# tester1.net
KiCad netlist of a schematic drawn in EAGLE
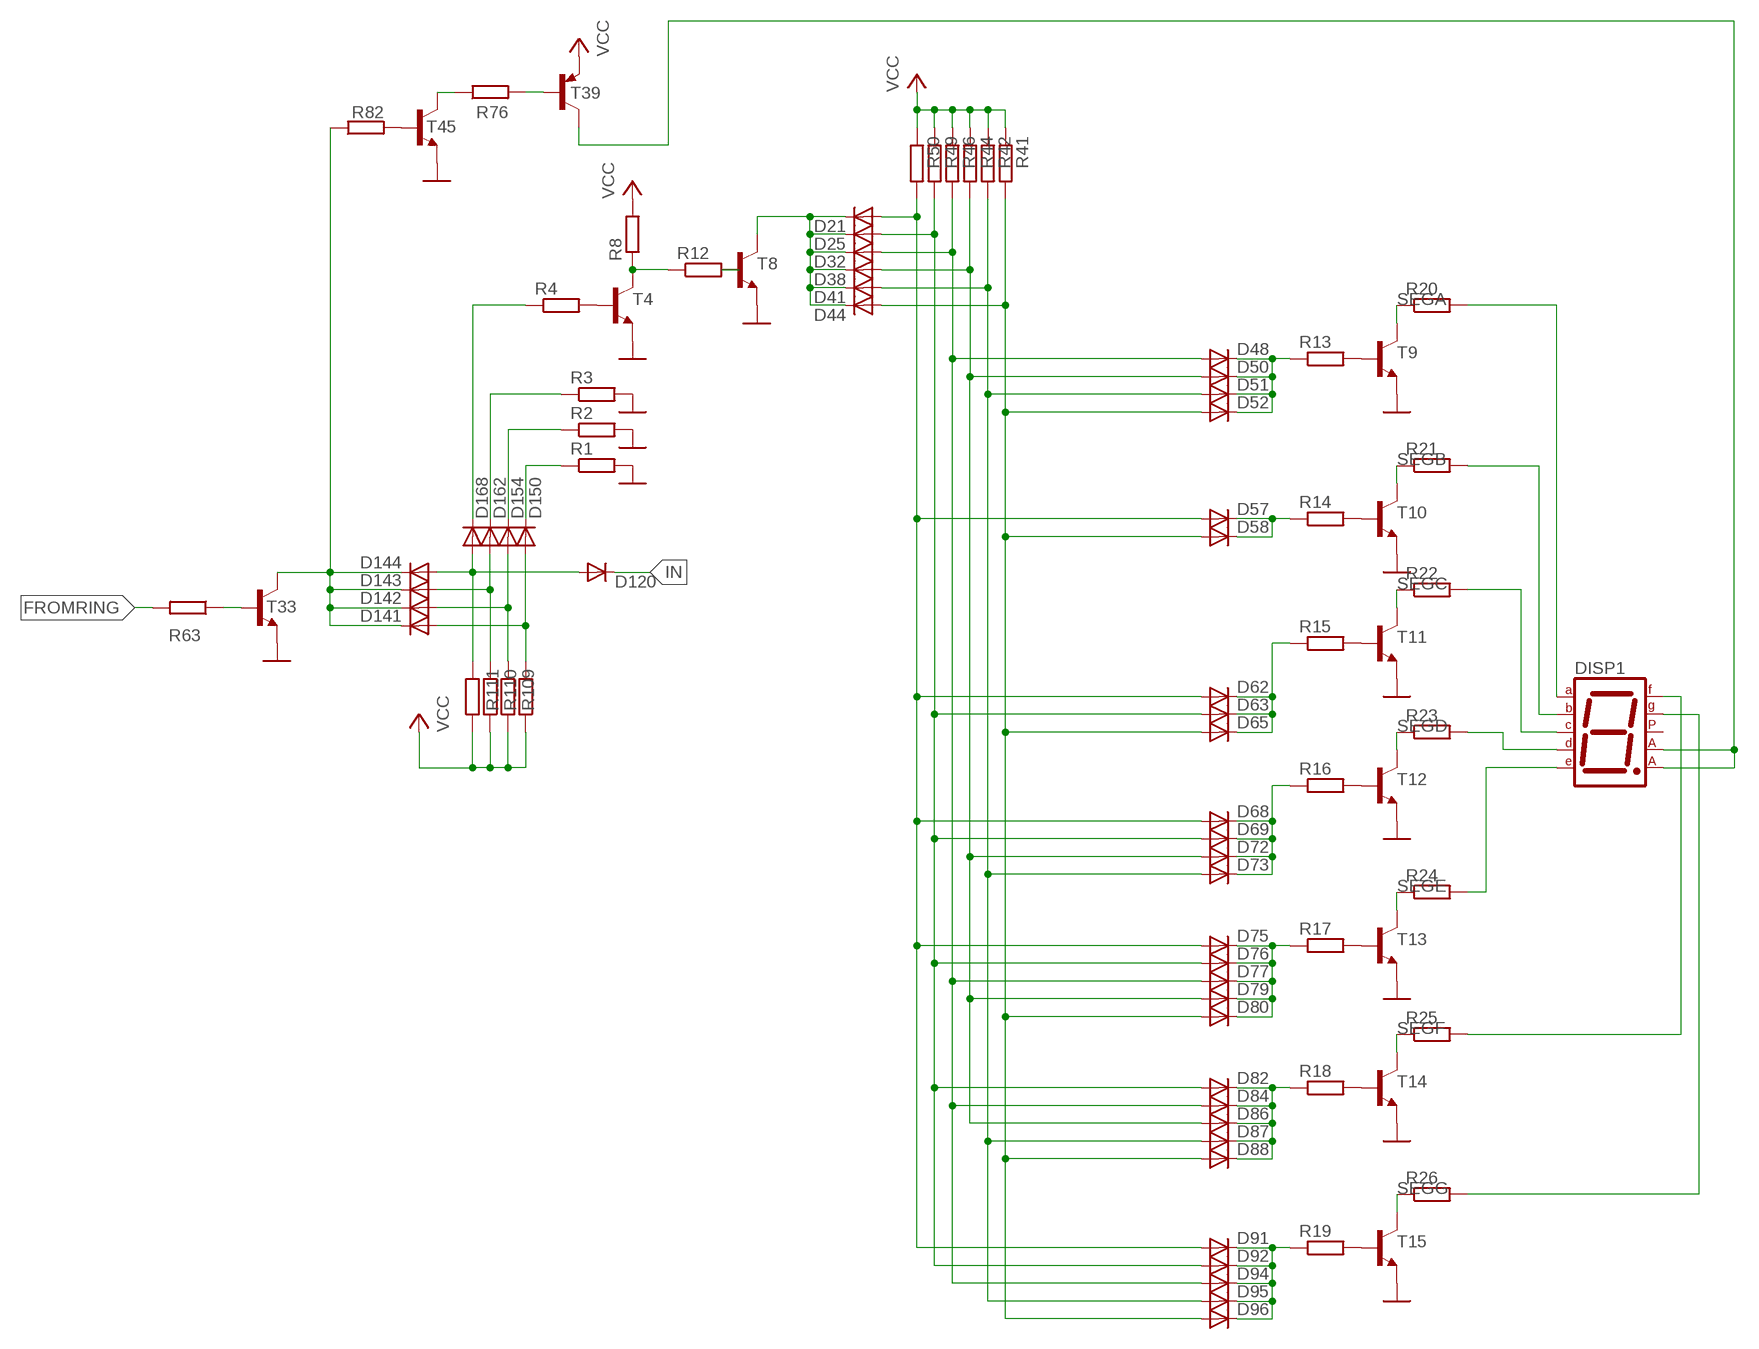
[diagram p0: schematic, sheet 1]

(export (version "E")
  (design (tool "Eeschema 10.0.6"))
  (components
    (comp (ref "D21")
      (value "SMALL_DIODEDO35-7")
      (footprint "eagle-import:DO35-7")
      (libsource (lib "eagle-import") (part "SMALL_DIODEDO35-7"))
    )
    (comp (ref "D25")
      (value "SMALL_DIODEDO35-7")
      (footprint "eagle-import:DO35-7")
      (libsource (lib "eagle-import") (part "SMALL_DIODEDO35-7"))
    )
    (comp (ref "D32")
      (value "SMALL_DIODEDO35-7")
      (footprint "eagle-import:DO35-7")
      (libsource (lib "eagle-import") (part "SMALL_DIODEDO35-7"))
    )
    (comp (ref "D38")
      (value "SMALL_DIODEDO35-7")
      (footprint "eagle-import:DO35-7")
      (libsource (lib "eagle-import") (part "SMALL_DIODEDO35-7"))
    )
    (comp (ref "D41")
      (value "SMALL_DIODEDO35-7")
      (footprint "eagle-import:DO35-7")
      (libsource (lib "eagle-import") (part "SMALL_DIODEDO35-7"))
    )
    (comp (ref "D44")
      (value "SMALL_DIODEDO35-7")
      (footprint "eagle-import:DO35-7")
      (libsource (lib "eagle-import") (part "SMALL_DIODEDO35-7"))
    )
    (comp (ref "D48")
      (value "SMALL_DIODEDO35-7")
      (footprint "eagle-import:DO35-7")
      (libsource (lib "eagle-import") (part "SMALL_DIODEDO35-7"))
    )
    (comp (ref "D50")
      (value "SMALL_DIODEDO35-7")
      (footprint "eagle-import:DO35-7")
      (libsource (lib "eagle-import") (part "SMALL_DIODEDO35-7"))
    )
    (comp (ref "D51")
      (value "SMALL_DIODEDO35-7")
      (footprint "eagle-import:DO35-7")
      (libsource (lib "eagle-import") (part "SMALL_DIODEDO35-7"))
    )
    (comp (ref "D52")
      (value "SMALL_DIODEDO35-7")
      (footprint "eagle-import:DO35-7")
      (libsource (lib "eagle-import") (part "SMALL_DIODEDO35-7"))
    )
    (comp (ref "D57")
      (value "SMALL_DIODEDO35-7")
      (footprint "eagle-import:DO35-7")
      (libsource (lib "eagle-import") (part "SMALL_DIODEDO35-7"))
    )
    (comp (ref "D58")
      (value "SMALL_DIODEDO35-7")
      (footprint "eagle-import:DO35-7")
      (libsource (lib "eagle-import") (part "SMALL_DIODEDO35-7"))
    )
    (comp (ref "D62")
      (value "SMALL_DIODEDO35-7")
      (footprint "eagle-import:DO35-7")
      (libsource (lib "eagle-import") (part "SMALL_DIODEDO35-7"))
    )
    (comp (ref "D63")
      (value "SMALL_DIODEDO35-7")
      (footprint "eagle-import:DO35-7")
      (libsource (lib "eagle-import") (part "SMALL_DIODEDO35-7"))
    )
    (comp (ref "D65")
      (value "SMALL_DIODEDO35-7")
      (footprint "eagle-import:DO35-7")
      (libsource (lib "eagle-import") (part "SMALL_DIODEDO35-7"))
    )
    (comp (ref "D68")
      (value "SMALL_DIODEDO35-7")
      (footprint "eagle-import:DO35-7")
      (libsource (lib "eagle-import") (part "SMALL_DIODEDO35-7"))
    )
    (comp (ref "D69")
      (value "SMALL_DIODEDO35-7")
      (footprint "eagle-import:DO35-7")
      (libsource (lib "eagle-import") (part "SMALL_DIODEDO35-7"))
    )
    (comp (ref "D72")
      (value "SMALL_DIODEDO35-7")
      (footprint "eagle-import:DO35-7")
      (libsource (lib "eagle-import") (part "SMALL_DIODEDO35-7"))
    )
    (comp (ref "D73")
      (value "SMALL_DIODEDO35-7")
      (footprint "eagle-import:DO35-7")
      (libsource (lib "eagle-import") (part "SMALL_DIODEDO35-7"))
    )
    (comp (ref "D75")
      (value "SMALL_DIODEDO35-7")
      (footprint "eagle-import:DO35-7")
      (libsource (lib "eagle-import") (part "SMALL_DIODEDO35-7"))
    )
    (comp (ref "D76")
      (value "SMALL_DIODEDO35-7")
      (footprint "eagle-import:DO35-7")
      (libsource (lib "eagle-import") (part "SMALL_DIODEDO35-7"))
    )
    (comp (ref "D77")
      (value "SMALL_DIODEDO35-7")
      (footprint "eagle-import:DO35-7")
      (libsource (lib "eagle-import") (part "SMALL_DIODEDO35-7"))
    )
    (comp (ref "D79")
      (value "SMALL_DIODEDO35-7")
      (footprint "eagle-import:DO35-7")
      (libsource (lib "eagle-import") (part "SMALL_DIODEDO35-7"))
    )
    (comp (ref "D80")
      (value "SMALL_DIODEDO35-7")
      (footprint "eagle-import:DO35-7")
      (libsource (lib "eagle-import") (part "SMALL_DIODEDO35-7"))
    )
    (comp (ref "D82")
      (value "SMALL_DIODEDO35-7")
      (footprint "eagle-import:DO35-7")
      (libsource (lib "eagle-import") (part "SMALL_DIODEDO35-7"))
    )
    (comp (ref "D84")
      (value "SMALL_DIODEDO35-7")
      (footprint "eagle-import:DO35-7")
      (libsource (lib "eagle-import") (part "SMALL_DIODEDO35-7"))
    )
    (comp (ref "D86")
      (value "SMALL_DIODEDO35-7")
      (footprint "eagle-import:DO35-7")
      (libsource (lib "eagle-import") (part "SMALL_DIODEDO35-7"))
    )
    (comp (ref "D87")
      (value "SMALL_DIODEDO35-7")
      (footprint "eagle-import:DO35-7")
      (libsource (lib "eagle-import") (part "SMALL_DIODEDO35-7"))
    )
    (comp (ref "D88")
      (value "SMALL_DIODEDO35-7")
      (footprint "eagle-import:DO35-7")
      (libsource (lib "eagle-import") (part "SMALL_DIODEDO35-7"))
    )
    (comp (ref "D91")
      (value "SMALL_DIODEDO35-7")
      (footprint "eagle-import:DO35-7")
      (libsource (lib "eagle-import") (part "SMALL_DIODEDO35-7"))
    )
    (comp (ref "D92")
      (value "SMALL_DIODEDO35-7")
      (footprint "eagle-import:DO35-7")
      (libsource (lib "eagle-import") (part "SMALL_DIODEDO35-7"))
    )
    (comp (ref "D94")
      (value "SMALL_DIODEDO35-7")
      (footprint "eagle-import:DO35-7")
      (libsource (lib "eagle-import") (part "SMALL_DIODEDO35-7"))
    )
    (comp (ref "D95")
      (value "SMALL_DIODEDO35-7")
      (footprint "eagle-import:DO35-7")
      (libsource (lib "eagle-import") (part "SMALL_DIODEDO35-7"))
    )
    (comp (ref "D96")
      (value "SMALL_DIODEDO35-7")
      (footprint "eagle-import:DO35-7")
      (libsource (lib "eagle-import") (part "SMALL_DIODEDO35-7"))
    )
    (comp (ref "D120")
      (value "SMALL_DIODEDO35-7")
      (footprint "eagle-import:DO35-7")
      (libsource (lib "eagle-import") (part "SMALL_DIODEDO35-7"))
    )
    (comp (ref "D141")
      (value "SMALL_DIODEDO35-7")
      (footprint "eagle-import:DO35-7")
      (libsource (lib "eagle-import") (part "SMALL_DIODEDO35-7"))
    )
    (comp (ref "D142")
      (value "SMALL_DIODEDO35-7")
      (footprint "eagle-import:DO35-7")
      (libsource (lib "eagle-import") (part "SMALL_DIODEDO35-7"))
    )
    (comp (ref "D143")
      (value "SMALL_DIODEDO35-7")
      (footprint "eagle-import:DO35-7")
      (libsource (lib "eagle-import") (part "SMALL_DIODEDO35-7"))
    )
    (comp (ref "D144")
      (value "SMALL_DIODEDO35-7")
      (footprint "eagle-import:DO35-7")
      (libsource (lib "eagle-import") (part "SMALL_DIODEDO35-7"))
    )
    (comp (ref "D150")
      (value "SMALL_DIODEDO35-7")
      (footprint "eagle-import:DO35-7")
      (libsource (lib "eagle-import") (part "SMALL_DIODEDO35-7"))
    )
    (comp (ref "D154")
      (value "SMALL_DIODEDO35-7")
      (footprint "eagle-import:DO35-7")
      (libsource (lib "eagle-import") (part "SMALL_DIODEDO35-7"))
    )
    (comp (ref "D162")
      (value "SMALL_DIODEDO35-7")
      (footprint "eagle-import:DO35-7")
      (libsource (lib "eagle-import") (part "SMALL_DIODEDO35-7"))
    )
    (comp (ref "D168")
      (value "SMALL_DIODEDO35-7")
      (footprint "eagle-import:DO35-7")
      (libsource (lib "eagle-import") (part "SMALL_DIODEDO35-7"))
    )
    (comp (ref "DISP1")
      (value "7SEG-CA")
      (footprint "eagle-import:7SEG-13")
      (libsource (lib "eagle-import") (part "7SEG-CA"))
    )
    (comp (ref "R1")
      (value "RESISTOR7MM")
      (footprint "eagle-import:7MM_RESISTOR")
      (libsource (lib "eagle-import") (part "RESISTOR7MM"))
    )
    (comp (ref "R2")
      (value "RESISTOR7MM")
      (footprint "eagle-import:7MM_RESISTOR")
      (libsource (lib "eagle-import") (part "RESISTOR7MM"))
    )
    (comp (ref "R3")
      (value "RESISTOR7MM")
      (footprint "eagle-import:7MM_RESISTOR")
      (libsource (lib "eagle-import") (part "RESISTOR7MM"))
    )
    (comp (ref "R4")
      (value "RESISTOR7MM")
      (footprint "eagle-import:7MM_RESISTOR")
      (libsource (lib "eagle-import") (part "RESISTOR7MM"))
    )
    (comp (ref "R8")
      (value "RESISTOR7MM")
      (footprint "eagle-import:7MM_RESISTOR")
      (libsource (lib "eagle-import") (part "RESISTOR7MM"))
    )
    (comp (ref "R12")
      (value "RESISTOR7MM")
      (footprint "eagle-import:7MM_RESISTOR")
      (libsource (lib "eagle-import") (part "RESISTOR7MM"))
    )
    (comp (ref "R13")
      (value "RESISTOR7MM")
      (footprint "eagle-import:7MM_RESISTOR")
      (libsource (lib "eagle-import") (part "RESISTOR7MM"))
    )
    (comp (ref "R14")
      (value "RESISTOR7MM")
      (footprint "eagle-import:7MM_RESISTOR")
      (libsource (lib "eagle-import") (part "RESISTOR7MM"))
    )
    (comp (ref "R15")
      (value "RESISTOR7MM")
      (footprint "eagle-import:7MM_RESISTOR")
      (libsource (lib "eagle-import") (part "RESISTOR7MM"))
    )
    (comp (ref "R16")
      (value "RESISTOR7MM")
      (footprint "eagle-import:7MM_RESISTOR")
      (libsource (lib "eagle-import") (part "RESISTOR7MM"))
    )
    (comp (ref "R17")
      (value "RESISTOR7MM")
      (footprint "eagle-import:7MM_RESISTOR")
      (libsource (lib "eagle-import") (part "RESISTOR7MM"))
    )
    (comp (ref "R18")
      (value "RESISTOR7MM")
      (footprint "eagle-import:7MM_RESISTOR")
      (libsource (lib "eagle-import") (part "RESISTOR7MM"))
    )
    (comp (ref "R19")
      (value "RESISTOR7MM")
      (footprint "eagle-import:7MM_RESISTOR")
      (libsource (lib "eagle-import") (part "RESISTOR7MM"))
    )
    (comp (ref "R20")
      (value "RESISTOR7MM")
      (footprint "eagle-import:7MM_RESISTOR")
      (libsource (lib "eagle-import") (part "RESISTOR7MM"))
    )
    (comp (ref "R21")
      (value "RESISTOR7MM")
      (footprint "eagle-import:7MM_RESISTOR")
      (libsource (lib "eagle-import") (part "RESISTOR7MM"))
    )
    (comp (ref "R22")
      (value "RESISTOR7MM")
      (footprint "eagle-import:7MM_RESISTOR")
      (libsource (lib "eagle-import") (part "RESISTOR7MM"))
    )
    (comp (ref "R23")
      (value "RESISTOR7MM")
      (footprint "eagle-import:7MM_RESISTOR")
      (libsource (lib "eagle-import") (part "RESISTOR7MM"))
    )
    (comp (ref "R24")
      (value "RESISTOR7MM")
      (footprint "eagle-import:7MM_RESISTOR")
      (libsource (lib "eagle-import") (part "RESISTOR7MM"))
    )
    (comp (ref "R25")
      (value "RESISTOR7MM")
      (footprint "eagle-import:7MM_RESISTOR")
      (libsource (lib "eagle-import") (part "RESISTOR7MM"))
    )
    (comp (ref "R26")
      (value "RESISTOR7MM")
      (footprint "eagle-import:7MM_RESISTOR")
      (libsource (lib "eagle-import") (part "RESISTOR7MM"))
    )
    (comp (ref "R41")
      (value "RESISTOR7MM")
      (footprint "eagle-import:7MM_RESISTOR")
      (libsource (lib "eagle-import") (part "RESISTOR7MM"))
    )
    (comp (ref "R42")
      (value "RESISTOR7MM")
      (footprint "eagle-import:7MM_RESISTOR")
      (libsource (lib "eagle-import") (part "RESISTOR7MM"))
    )
    (comp (ref "R44")
      (value "RESISTOR7MM")
      (footprint "eagle-import:7MM_RESISTOR")
      (libsource (lib "eagle-import") (part "RESISTOR7MM"))
    )
    (comp (ref "R46")
      (value "RESISTOR7MM")
      (footprint "eagle-import:7MM_RESISTOR")
      (libsource (lib "eagle-import") (part "RESISTOR7MM"))
    )
    (comp (ref "R49")
      (value "RESISTOR7MM")
      (footprint "eagle-import:7MM_RESISTOR")
      (libsource (lib "eagle-import") (part "RESISTOR7MM"))
    )
    (comp (ref "R50")
      (value "RESISTOR7MM")
      (footprint "eagle-import:7MM_RESISTOR")
      (libsource (lib "eagle-import") (part "RESISTOR7MM"))
    )
    (comp (ref "R63")
      (value "RESISTOR7MM")
      (footprint "eagle-import:7MM_RESISTOR")
      (libsource (lib "eagle-import") (part "RESISTOR7MM"))
    )
    (comp (ref "R76")
      (value "RESISTOR7MM")
      (footprint "eagle-import:7MM_RESISTOR")
      (libsource (lib "eagle-import") (part "RESISTOR7MM"))
    )
    (comp (ref "R82")
      (value "RESISTOR7MM")
      (footprint "eagle-import:7MM_RESISTOR")
      (libsource (lib "eagle-import") (part "RESISTOR7MM"))
    )
    (comp (ref "R108")
      (value "RESISTOR7MM")
      (footprint "eagle-import:7MM_RESISTOR")
      (libsource (lib "eagle-import") (part "RESISTOR7MM"))
    )
    (comp (ref "R109")
      (value "RESISTOR7MM")
      (footprint "eagle-import:7MM_RESISTOR")
      (libsource (lib "eagle-import") (part "RESISTOR7MM"))
    )
    (comp (ref "R110")
      (value "RESISTOR7MM")
      (footprint "eagle-import:7MM_RESISTOR")
      (libsource (lib "eagle-import") (part "RESISTOR7MM"))
    )
    (comp (ref "R111")
      (value "RESISTOR7MM")
      (footprint "eagle-import:7MM_RESISTOR")
      (libsource (lib "eagle-import") (part "RESISTOR7MM"))
    )
    (comp (ref "T4")
      (value "BC547B-NPN-TO92-CBE")
      (footprint "eagle-import:TO92-CBE")
      (libsource (lib "eagle-import") (part "-NPN-TO92-CBEBC547B"))
    )
    (comp (ref "T8")
      (value "BC547B-NPN-TO92-CBE")
      (footprint "eagle-import:TO92-CBE")
      (libsource (lib "eagle-import") (part "-NPN-TO92-CBEBC547B"))
    )
    (comp (ref "T9")
      (value "BC547B-NPN-TO92-CBE")
      (footprint "eagle-import:TO92-CBE")
      (libsource (lib "eagle-import") (part "-NPN-TO92-CBEBC547B"))
    )
    (comp (ref "T10")
      (value "BC547B-NPN-TO92-CBE")
      (footprint "eagle-import:TO92-CBE")
      (libsource (lib "eagle-import") (part "-NPN-TO92-CBEBC547B"))
    )
    (comp (ref "T11")
      (value "BC547B-NPN-TO92-CBE")
      (footprint "eagle-import:TO92-CBE")
      (libsource (lib "eagle-import") (part "-NPN-TO92-CBEBC547B"))
    )
    (comp (ref "T12")
      (value "BC547B-NPN-TO92-CBE")
      (footprint "eagle-import:TO92-CBE")
      (libsource (lib "eagle-import") (part "-NPN-TO92-CBEBC547B"))
    )
    (comp (ref "T13")
      (value "BC547B-NPN-TO92-CBE")
      (footprint "eagle-import:TO92-CBE")
      (libsource (lib "eagle-import") (part "-NPN-TO92-CBEBC547B"))
    )
    (comp (ref "T14")
      (value "BC547B-NPN-TO92-CBE")
      (footprint "eagle-import:TO92-CBE")
      (libsource (lib "eagle-import") (part "-NPN-TO92-CBEBC547B"))
    )
    (comp (ref "T15")
      (value "BC547B-NPN-TO92-CBE")
      (footprint "eagle-import:TO92-CBE")
      (libsource (lib "eagle-import") (part "-NPN-TO92-CBEBC547B"))
    )
    (comp (ref "T33")
      (value "BC547B-NPN-TO92-CBE")
      (footprint "eagle-import:TO92-CBE")
      (libsource (lib "eagle-import") (part "-NPN-TO92-CBEBC547B"))
    )
    (comp (ref "T39")
      (value "BC557B-PNP-TO92-EBC")
      (footprint "eagle-import:TO92-EBC")
      (libsource (lib "eagle-import") (part "-PNP-TO92-EBCBC557B"))
    )
    (comp (ref "T45")
      (value "BC547B-NPN-TO92-CBE")
      (footprint "eagle-import:TO92-CBE")
      (libsource (lib "eagle-import") (part "-NPN-TO92-CBEBC547B"))
    )
  )
  (nets
    (net (code "1") (name "/SEGA") (class "Default")
      (node (ref "R20") (pin "1") (pinfunction "1_1") (pintype "passive"))
      (node (ref "T9") (pin "C") (pinfunction "C_C") (pintype "passive"))
    )
    (net (code "2") (name "/SEGB") (class "Default")
      (node (ref "R21") (pin "1") (pinfunction "1_1") (pintype "passive"))
      (node (ref "T10") (pin "C") (pinfunction "C_C") (pintype "passive"))
    )
    (net (code "3") (name "/SEGC") (class "Default")
      (node (ref "R22") (pin "1") (pinfunction "1_1") (pintype "passive"))
      (node (ref "T11") (pin "C") (pinfunction "C_C") (pintype "passive"))
    )
    (net (code "4") (name "/SEGD") (class "Default")
      (node (ref "R23") (pin "1") (pinfunction "1_1") (pintype "passive"))
      (node (ref "T12") (pin "C") (pinfunction "C_C") (pintype "passive"))
    )
    (net (code "5") (name "/SEGE") (class "Default")
      (node (ref "R24") (pin "1") (pinfunction "1_1") (pintype "passive"))
      (node (ref "T13") (pin "C") (pinfunction "C_C") (pintype "passive"))
    )
    (net (code "6") (name "/SEGF") (class "Default")
      (node (ref "R25") (pin "1") (pinfunction "1_1") (pintype "passive"))
      (node (ref "T14") (pin "C") (pinfunction "C_C") (pintype "passive"))
    )
    (net (code "7") (name "/SEGG") (class "Default")
      (node (ref "R26") (pin "1") (pinfunction "1_1") (pintype "passive"))
      (node (ref "T15") (pin "C") (pinfunction "C_C") (pintype "passive"))
    )
    (net (code "8") (name "FROMRING") (class "Default")
      (node (ref "R63") (pin "2") (pinfunction "2_2") (pintype "passive"))
    )
    (net (code "9") (name "GND") (class "Default")
      (node (ref "R1") (pin "2") (pinfunction "2_2") (pintype "passive"))
      (node (ref "R2") (pin "2") (pinfunction "2_2") (pintype "passive"))
      (node (ref "R3") (pin "2") (pinfunction "2_2") (pintype "passive"))
      (node (ref "T10") (pin "E") (pinfunction "E_E") (pintype "passive"))
      (node (ref "T11") (pin "E") (pinfunction "E_E") (pintype "passive"))
      (node (ref "T12") (pin "E") (pinfunction "E_E") (pintype "passive"))
      (node (ref "T13") (pin "E") (pinfunction "E_E") (pintype "passive"))
      (node (ref "T14") (pin "E") (pinfunction "E_E") (pintype "passive"))
      (node (ref "T15") (pin "E") (pinfunction "E_E") (pintype "passive"))
      (node (ref "T33") (pin "E") (pinfunction "E_E") (pintype "passive"))
      (node (ref "T4") (pin "E") (pinfunction "E_E") (pintype "passive"))
      (node (ref "T45") (pin "E") (pinfunction "E_E") (pintype "passive"))
      (node (ref "T8") (pin "E") (pinfunction "E_E") (pintype "passive"))
      (node (ref "T9") (pin "E") (pinfunction "E_E") (pintype "passive"))
    )
    (net (code "10") (name "IN") (class "Default")
      (node (ref "D120") (pin "C") (pinfunction "C_C") (pintype "passive"))
    )
    (net (code "11") (name "Net-(D21-PadA)") (class "Default")
      (node (ref "D21") (pin "A") (pinfunction "A_A") (pintype "passive"))
      (node (ref "D57") (pin "A") (pinfunction "A_A") (pintype "passive"))
      (node (ref "D62") (pin "A") (pinfunction "A_A") (pintype "passive"))
      (node (ref "D68") (pin "A") (pinfunction "A_A") (pintype "passive"))
      (node (ref "D75") (pin "A") (pinfunction "A_A") (pintype "passive"))
      (node (ref "D91") (pin "A") (pinfunction "A_A") (pintype "passive"))
      (node (ref "R50") (pin "2") (pinfunction "2_2") (pintype "passive"))
    )
    (net (code "12") (name "Net-(D21-PadC)") (class "Default")
      (node (ref "D21") (pin "C") (pinfunction "C_C") (pintype "passive"))
      (node (ref "D25") (pin "C") (pinfunction "C_C") (pintype "passive"))
      (node (ref "D32") (pin "C") (pinfunction "C_C") (pintype "passive"))
      (node (ref "D38") (pin "C") (pinfunction "C_C") (pintype "passive"))
      (node (ref "D41") (pin "C") (pinfunction "C_C") (pintype "passive"))
      (node (ref "D44") (pin "C") (pinfunction "C_C") (pintype "passive"))
      (node (ref "T8") (pin "C") (pinfunction "C_C") (pintype "passive"))
    )
    (net (code "13") (name "Net-(D25-PadA)") (class "Default")
      (node (ref "D25") (pin "A") (pinfunction "A_A") (pintype "passive"))
      (node (ref "D63") (pin "A") (pinfunction "A_A") (pintype "passive"))
      (node (ref "D69") (pin "A") (pinfunction "A_A") (pintype "passive"))
      (node (ref "D76") (pin "A") (pinfunction "A_A") (pintype "passive"))
      (node (ref "D82") (pin "A") (pinfunction "A_A") (pintype "passive"))
      (node (ref "D92") (pin "A") (pinfunction "A_A") (pintype "passive"))
      (node (ref "R49") (pin "2") (pinfunction "2_2") (pintype "passive"))
    )
    (net (code "14") (name "Net-(D32-PadA)") (class "Default")
      (node (ref "D32") (pin "A") (pinfunction "A_A") (pintype "passive"))
      (node (ref "D48") (pin "A") (pinfunction "A_A") (pintype "passive"))
      (node (ref "D77") (pin "A") (pinfunction "A_A") (pintype "passive"))
      (node (ref "D84") (pin "A") (pinfunction "A_A") (pintype "passive"))
      (node (ref "D94") (pin "A") (pinfunction "A_A") (pintype "passive"))
      (node (ref "R46") (pin "2") (pinfunction "2_2") (pintype "passive"))
    )
    (net (code "15") (name "Net-(D38-PadA)") (class "Default")
      (node (ref "D38") (pin "A") (pinfunction "A_A") (pintype "passive"))
      (node (ref "D50") (pin "A") (pinfunction "A_A") (pintype "passive"))
      (node (ref "D72") (pin "A") (pinfunction "A_A") (pintype "passive"))
      (node (ref "D79") (pin "A") (pinfunction "A_A") (pintype "passive"))
      (node (ref "D86") (pin "A") (pinfunction "A_A") (pintype "passive"))
      (node (ref "R44") (pin "2") (pinfunction "2_2") (pintype "passive"))
    )
    (net (code "16") (name "Net-(D41-PadA)") (class "Default")
      (node (ref "D41") (pin "A") (pinfunction "A_A") (pintype "passive"))
      (node (ref "D51") (pin "A") (pinfunction "A_A") (pintype "passive"))
      (node (ref "D73") (pin "A") (pinfunction "A_A") (pintype "passive"))
      (node (ref "D87") (pin "A") (pinfunction "A_A") (pintype "passive"))
      (node (ref "D95") (pin "A") (pinfunction "A_A") (pintype "passive"))
      (node (ref "R42") (pin "2") (pinfunction "2_2") (pintype "passive"))
    )
    (net (code "17") (name "Net-(D44-PadA)") (class "Default")
      (node (ref "D44") (pin "A") (pinfunction "A_A") (pintype "passive"))
      (node (ref "D52") (pin "A") (pinfunction "A_A") (pintype "passive"))
      (node (ref "D58") (pin "A") (pinfunction "A_A") (pintype "passive"))
      (node (ref "D65") (pin "A") (pinfunction "A_A") (pintype "passive"))
      (node (ref "D80") (pin "A") (pinfunction "A_A") (pintype "passive"))
      (node (ref "D88") (pin "A") (pinfunction "A_A") (pintype "passive"))
      (node (ref "D96") (pin "A") (pinfunction "A_A") (pintype "passive"))
      (node (ref "R41") (pin "2") (pinfunction "2_2") (pintype "passive"))
    )
    (net (code "18") (name "Net-(D48-PadC)") (class "Default")
      (node (ref "D48") (pin "C") (pinfunction "C_C") (pintype "passive"))
      (node (ref "D50") (pin "C") (pinfunction "C_C") (pintype "passive"))
      (node (ref "D51") (pin "C") (pinfunction "C_C") (pintype "passive"))
      (node (ref "D52") (pin "C") (pinfunction "C_C") (pintype "passive"))
      (node (ref "R13") (pin "1") (pinfunction "1_1") (pintype "passive"))
    )
    (net (code "19") (name "Net-(D57-PadC)") (class "Default")
      (node (ref "D57") (pin "C") (pinfunction "C_C") (pintype "passive"))
      (node (ref "D58") (pin "C") (pinfunction "C_C") (pintype "passive"))
      (node (ref "R14") (pin "1") (pinfunction "1_1") (pintype "passive"))
    )
    (net (code "20") (name "Net-(D62-PadC)") (class "Default")
      (node (ref "D62") (pin "C") (pinfunction "C_C") (pintype "passive"))
      (node (ref "D63") (pin "C") (pinfunction "C_C") (pintype "passive"))
      (node (ref "D65") (pin "C") (pinfunction "C_C") (pintype "passive"))
      (node (ref "R15") (pin "1") (pinfunction "1_1") (pintype "passive"))
    )
    (net (code "21") (name "Net-(D68-PadC)") (class "Default")
      (node (ref "D68") (pin "C") (pinfunction "C_C") (pintype "passive"))
      (node (ref "D69") (pin "C") (pinfunction "C_C") (pintype "passive"))
      (node (ref "D72") (pin "C") (pinfunction "C_C") (pintype "passive"))
      (node (ref "D73") (pin "C") (pinfunction "C_C") (pintype "passive"))
      (node (ref "R16") (pin "1") (pinfunction "1_1") (pintype "passive"))
    )
    (net (code "22") (name "Net-(D75-PadC)") (class "Default")
      (node (ref "D75") (pin "C") (pinfunction "C_C") (pintype "passive"))
      (node (ref "D76") (pin "C") (pinfunction "C_C") (pintype "passive"))
      (node (ref "D77") (pin "C") (pinfunction "C_C") (pintype "passive"))
      (node (ref "D79") (pin "C") (pinfunction "C_C") (pintype "passive"))
      (node (ref "D80") (pin "C") (pinfunction "C_C") (pintype "passive"))
      (node (ref "R17") (pin "1") (pinfunction "1_1") (pintype "passive"))
    )
    (net (code "23") (name "Net-(D82-PadC)") (class "Default")
      (node (ref "D82") (pin "C") (pinfunction "C_C") (pintype "passive"))
      (node (ref "D84") (pin "C") (pinfunction "C_C") (pintype "passive"))
      (node (ref "D86") (pin "C") (pinfunction "C_C") (pintype "passive"))
      (node (ref "D87") (pin "C") (pinfunction "C_C") (pintype "passive"))
      (node (ref "D88") (pin "C") (pinfunction "C_C") (pintype "passive"))
      (node (ref "R18") (pin "1") (pinfunction "1_1") (pintype "passive"))
    )
    (net (code "24") (name "Net-(D91-PadC)") (class "Default")
      (node (ref "D91") (pin "C") (pinfunction "C_C") (pintype "passive"))
      (node (ref "D92") (pin "C") (pinfunction "C_C") (pintype "passive"))
      (node (ref "D94") (pin "C") (pinfunction "C_C") (pintype "passive"))
      (node (ref "D95") (pin "C") (pinfunction "C_C") (pintype "passive"))
      (node (ref "D96") (pin "C") (pinfunction "C_C") (pintype "passive"))
      (node (ref "R19") (pin "1") (pinfunction "1_1") (pintype "passive"))
    )
    (net (code "25") (name "Net-(D120-PadA)") (class "Default")
      (node (ref "D120") (pin "A") (pinfunction "A_A") (pintype "passive"))
      (node (ref "D144") (pin "A") (pinfunction "A_A") (pintype "passive"))
      (node (ref "D168") (pin "A") (pinfunction "A_A") (pintype "passive"))
      (node (ref "R111") (pin "2") (pinfunction "2_2") (pintype "passive"))
    )
    (net (code "26") (name "Net-(D141-PadA)") (class "Default")
      (node (ref "D141") (pin "A") (pinfunction "A_A") (pintype "passive"))
      (node (ref "D150") (pin "A") (pinfunction "A_A") (pintype "passive"))
      (node (ref "R108") (pin "2") (pinfunction "2_2") (pintype "passive"))
    )
    (net (code "27") (name "Net-(D141-PadC)") (class "Default")
      (node (ref "D141") (pin "C") (pinfunction "C_C") (pintype "passive"))
      (node (ref "D142") (pin "C") (pinfunction "C_C") (pintype "passive"))
      (node (ref "D143") (pin "C") (pinfunction "C_C") (pintype "passive"))
      (node (ref "D144") (pin "C") (pinfunction "C_C") (pintype "passive"))
      (node (ref "R82") (pin "1") (pinfunction "1_1") (pintype "passive"))
      (node (ref "T33") (pin "C") (pinfunction "C_C") (pintype "passive"))
    )
    (net (code "28") (name "Net-(D142-PadA)") (class "Default")
      (node (ref "D142") (pin "A") (pinfunction "A_A") (pintype "passive"))
      (node (ref "D154") (pin "A") (pinfunction "A_A") (pintype "passive"))
      (node (ref "R109") (pin "2") (pinfunction "2_2") (pintype "passive"))
    )
    (net (code "29") (name "Net-(D143-PadA)") (class "Default")
      (node (ref "D143") (pin "A") (pinfunction "A_A") (pintype "passive"))
      (node (ref "D162") (pin "A") (pinfunction "A_A") (pintype "passive"))
      (node (ref "R110") (pin "2") (pinfunction "2_2") (pintype "passive"))
    )
    (net (code "30") (name "Net-(D150-PadC)") (class "Default")
      (node (ref "D150") (pin "C") (pinfunction "C_C") (pintype "passive"))
      (node (ref "R1") (pin "1") (pinfunction "1_1") (pintype "passive"))
    )
    (net (code "31") (name "Net-(D154-PadC)") (class "Default")
      (node (ref "D154") (pin "C") (pinfunction "C_C") (pintype "passive"))
      (node (ref "R2") (pin "1") (pinfunction "1_1") (pintype "passive"))
    )
    (net (code "32") (name "Net-(D162-PadC)") (class "Default")
      (node (ref "D162") (pin "C") (pinfunction "C_C") (pintype "passive"))
      (node (ref "R3") (pin "1") (pinfunction "1_1") (pintype "passive"))
    )
    (net (code "33") (name "Net-(D168-PadC)") (class "Default")
      (node (ref "D168") (pin "C") (pinfunction "C_C") (pintype "passive"))
      (node (ref "R4") (pin "1") (pinfunction "1_1") (pintype "passive"))
    )
    (net (code "34") (name "Net-(DISP1-A)") (class "Default")
      (node (ref "DISP1") (pin "7") (pinfunction "A_7") (pintype "passive"))
      (node (ref "R20") (pin "2") (pinfunction "2_2") (pintype "passive"))
    )
    (net (code "35") (name "Net-(DISP1-B)") (class "Default")
      (node (ref "DISP1") (pin "6") (pinfunction "B_6") (pintype "passive"))
      (node (ref "R21") (pin "2") (pinfunction "2_2") (pintype "passive"))
    )
    (net (code "36") (name "Net-(DISP1-C)") (class "Default")
      (node (ref "DISP1") (pin "4") (pinfunction "C_4") (pintype "passive"))
      (node (ref "R22") (pin "2") (pinfunction "2_2") (pintype "passive"))
    )
    (net (code "37") (name "Net-(DISP1-CA1)") (class "Default")
      (node (ref "DISP1") (pin "3") (pinfunction "CA1_3") (pintype "passive"))
      (node (ref "DISP1") (pin "8") (pinfunction "CA2_8") (pintype "passive"))
      (node (ref "T39") (pin "C") (pinfunction "C_C") (pintype "passive"))
    )
    (net (code "38") (name "Net-(DISP1-D)") (class "Default")
      (node (ref "DISP1") (pin "2") (pinfunction "D_2") (pintype "passive"))
      (node (ref "R23") (pin "2") (pinfunction "2_2") (pintype "passive"))
    )
    (net (code "39") (name "Net-(DISP1-E)") (class "Default")
      (node (ref "DISP1") (pin "1") (pinfunction "E_1") (pintype "passive"))
      (node (ref "R24") (pin "2") (pinfunction "2_2") (pintype "passive"))
    )
    (net (code "40") (name "Net-(DISP1-F)") (class "Default")
      (node (ref "DISP1") (pin "9") (pinfunction "F_9") (pintype "passive"))
      (node (ref "R25") (pin "2") (pinfunction "2_2") (pintype "passive"))
    )
    (net (code "41") (name "Net-(DISP1-G)") (class "Default")
      (node (ref "DISP1") (pin "10") (pinfunction "G_10") (pintype "passive"))
      (node (ref "R26") (pin "2") (pinfunction "2_2") (pintype "passive"))
    )
    (net (code "42") (name "Net-(R4-Pad2)") (class "Default")
      (node (ref "R4") (pin "2") (pinfunction "2_2") (pintype "passive"))
      (node (ref "T4") (pin "B") (pinfunction "B_B") (pintype "passive"))
    )
    (net (code "43") (name "Net-(R12-Pad1)") (class "Default")
      (node (ref "R12") (pin "1") (pinfunction "1_1") (pintype "passive"))
      (node (ref "R8") (pin "1") (pinfunction "1_1") (pintype "passive"))
      (node (ref "T4") (pin "C") (pinfunction "C_C") (pintype "passive"))
    )
    (net (code "44") (name "Net-(R12-Pad2)") (class "Default")
      (node (ref "R12") (pin "2") (pinfunction "2_2") (pintype "passive"))
      (node (ref "T8") (pin "B") (pinfunction "B_B") (pintype "passive"))
    )
    (net (code "45") (name "Net-(R13-Pad2)") (class "Default")
      (node (ref "R13") (pin "2") (pinfunction "2_2") (pintype "passive"))
      (node (ref "T9") (pin "B") (pinfunction "B_B") (pintype "passive"))
    )
    (net (code "46") (name "Net-(R14-Pad2)") (class "Default")
      (node (ref "R14") (pin "2") (pinfunction "2_2") (pintype "passive"))
      (node (ref "T10") (pin "B") (pinfunction "B_B") (pintype "passive"))
    )
    (net (code "47") (name "Net-(R15-Pad2)") (class "Default")
      (node (ref "R15") (pin "2") (pinfunction "2_2") (pintype "passive"))
      (node (ref "T11") (pin "B") (pinfunction "B_B") (pintype "passive"))
    )
    (net (code "48") (name "Net-(R16-Pad2)") (class "Default")
      (node (ref "R16") (pin "2") (pinfunction "2_2") (pintype "passive"))
      (node (ref "T12") (pin "B") (pinfunction "B_B") (pintype "passive"))
    )
    (net (code "49") (name "Net-(R17-Pad2)") (class "Default")
      (node (ref "R17") (pin "2") (pinfunction "2_2") (pintype "passive"))
      (node (ref "T13") (pin "B") (pinfunction "B_B") (pintype "passive"))
    )
    (net (code "50") (name "Net-(R18-Pad2)") (class "Default")
      (node (ref "R18") (pin "2") (pinfunction "2_2") (pintype "passive"))
      (node (ref "T14") (pin "B") (pinfunction "B_B") (pintype "passive"))
    )
    (net (code "51") (name "Net-(R19-Pad2)") (class "Default")
      (node (ref "R19") (pin "2") (pinfunction "2_2") (pintype "passive"))
      (node (ref "T15") (pin "B") (pinfunction "B_B") (pintype "passive"))
    )
    (net (code "52") (name "Net-(R63-Pad1)") (class "Default")
      (node (ref "R63") (pin "1") (pinfunction "1_1") (pintype "passive"))
      (node (ref "T33") (pin "B") (pinfunction "B_B") (pintype "passive"))
    )
    (net (code "53") (name "Net-(R76-Pad1)") (class "Default")
      (node (ref "R76") (pin "1") (pinfunction "1_1") (pintype "passive"))
      (node (ref "T45") (pin "C") (pinfunction "C_C") (pintype "passive"))
    )
    (net (code "54") (name "Net-(R76-Pad2)") (class "Default")
      (node (ref "R76") (pin "2") (pinfunction "2_2") (pintype "passive"))
      (node (ref "T39") (pin "B") (pinfunction "B_B") (pintype "passive"))
    )
    (net (code "55") (name "Net-(R82-Pad2)") (class "Default")
      (node (ref "R82") (pin "2") (pinfunction "2_2") (pintype "passive"))
      (node (ref "T45") (pin "B") (pinfunction "B_B") (pintype "passive"))
    )
    (net (code "56") (name "VCC") (class "Default")
      (node (ref "R108") (pin "1") (pinfunction "1_1") (pintype "passive"))
      (node (ref "R109") (pin "1") (pinfunction "1_1") (pintype "passive"))
      (node (ref "R110") (pin "1") (pinfunction "1_1") (pintype "passive"))
      (node (ref "R111") (pin "1") (pinfunction "1_1") (pintype "passive"))
      (node (ref "R41") (pin "1") (pinfunction "1_1") (pintype "passive"))
      (node (ref "R42") (pin "1") (pinfunction "1_1") (pintype "passive"))
      (node (ref "R44") (pin "1") (pinfunction "1_1") (pintype "passive"))
      (node (ref "R46") (pin "1") (pinfunction "1_1") (pintype "passive"))
      (node (ref "R49") (pin "1") (pinfunction "1_1") (pintype "passive"))
      (node (ref "R50") (pin "1") (pinfunction "1_1") (pintype "passive"))
      (node (ref "R8") (pin "2") (pinfunction "2_2") (pintype "passive"))
      (node (ref "T39") (pin "E") (pinfunction "E_E") (pintype "passive"))
    )
    (net (code "57") (name "unconnected-(DISP1-DP-Pad5)") (class "Default")
      (node (ref "DISP1") (pin "5") (pinfunction "DP_5") (pintype "passive"))
    )
  )
)
